# BPF.net
KiCad netlist of a schematic drawn in Altium Designer
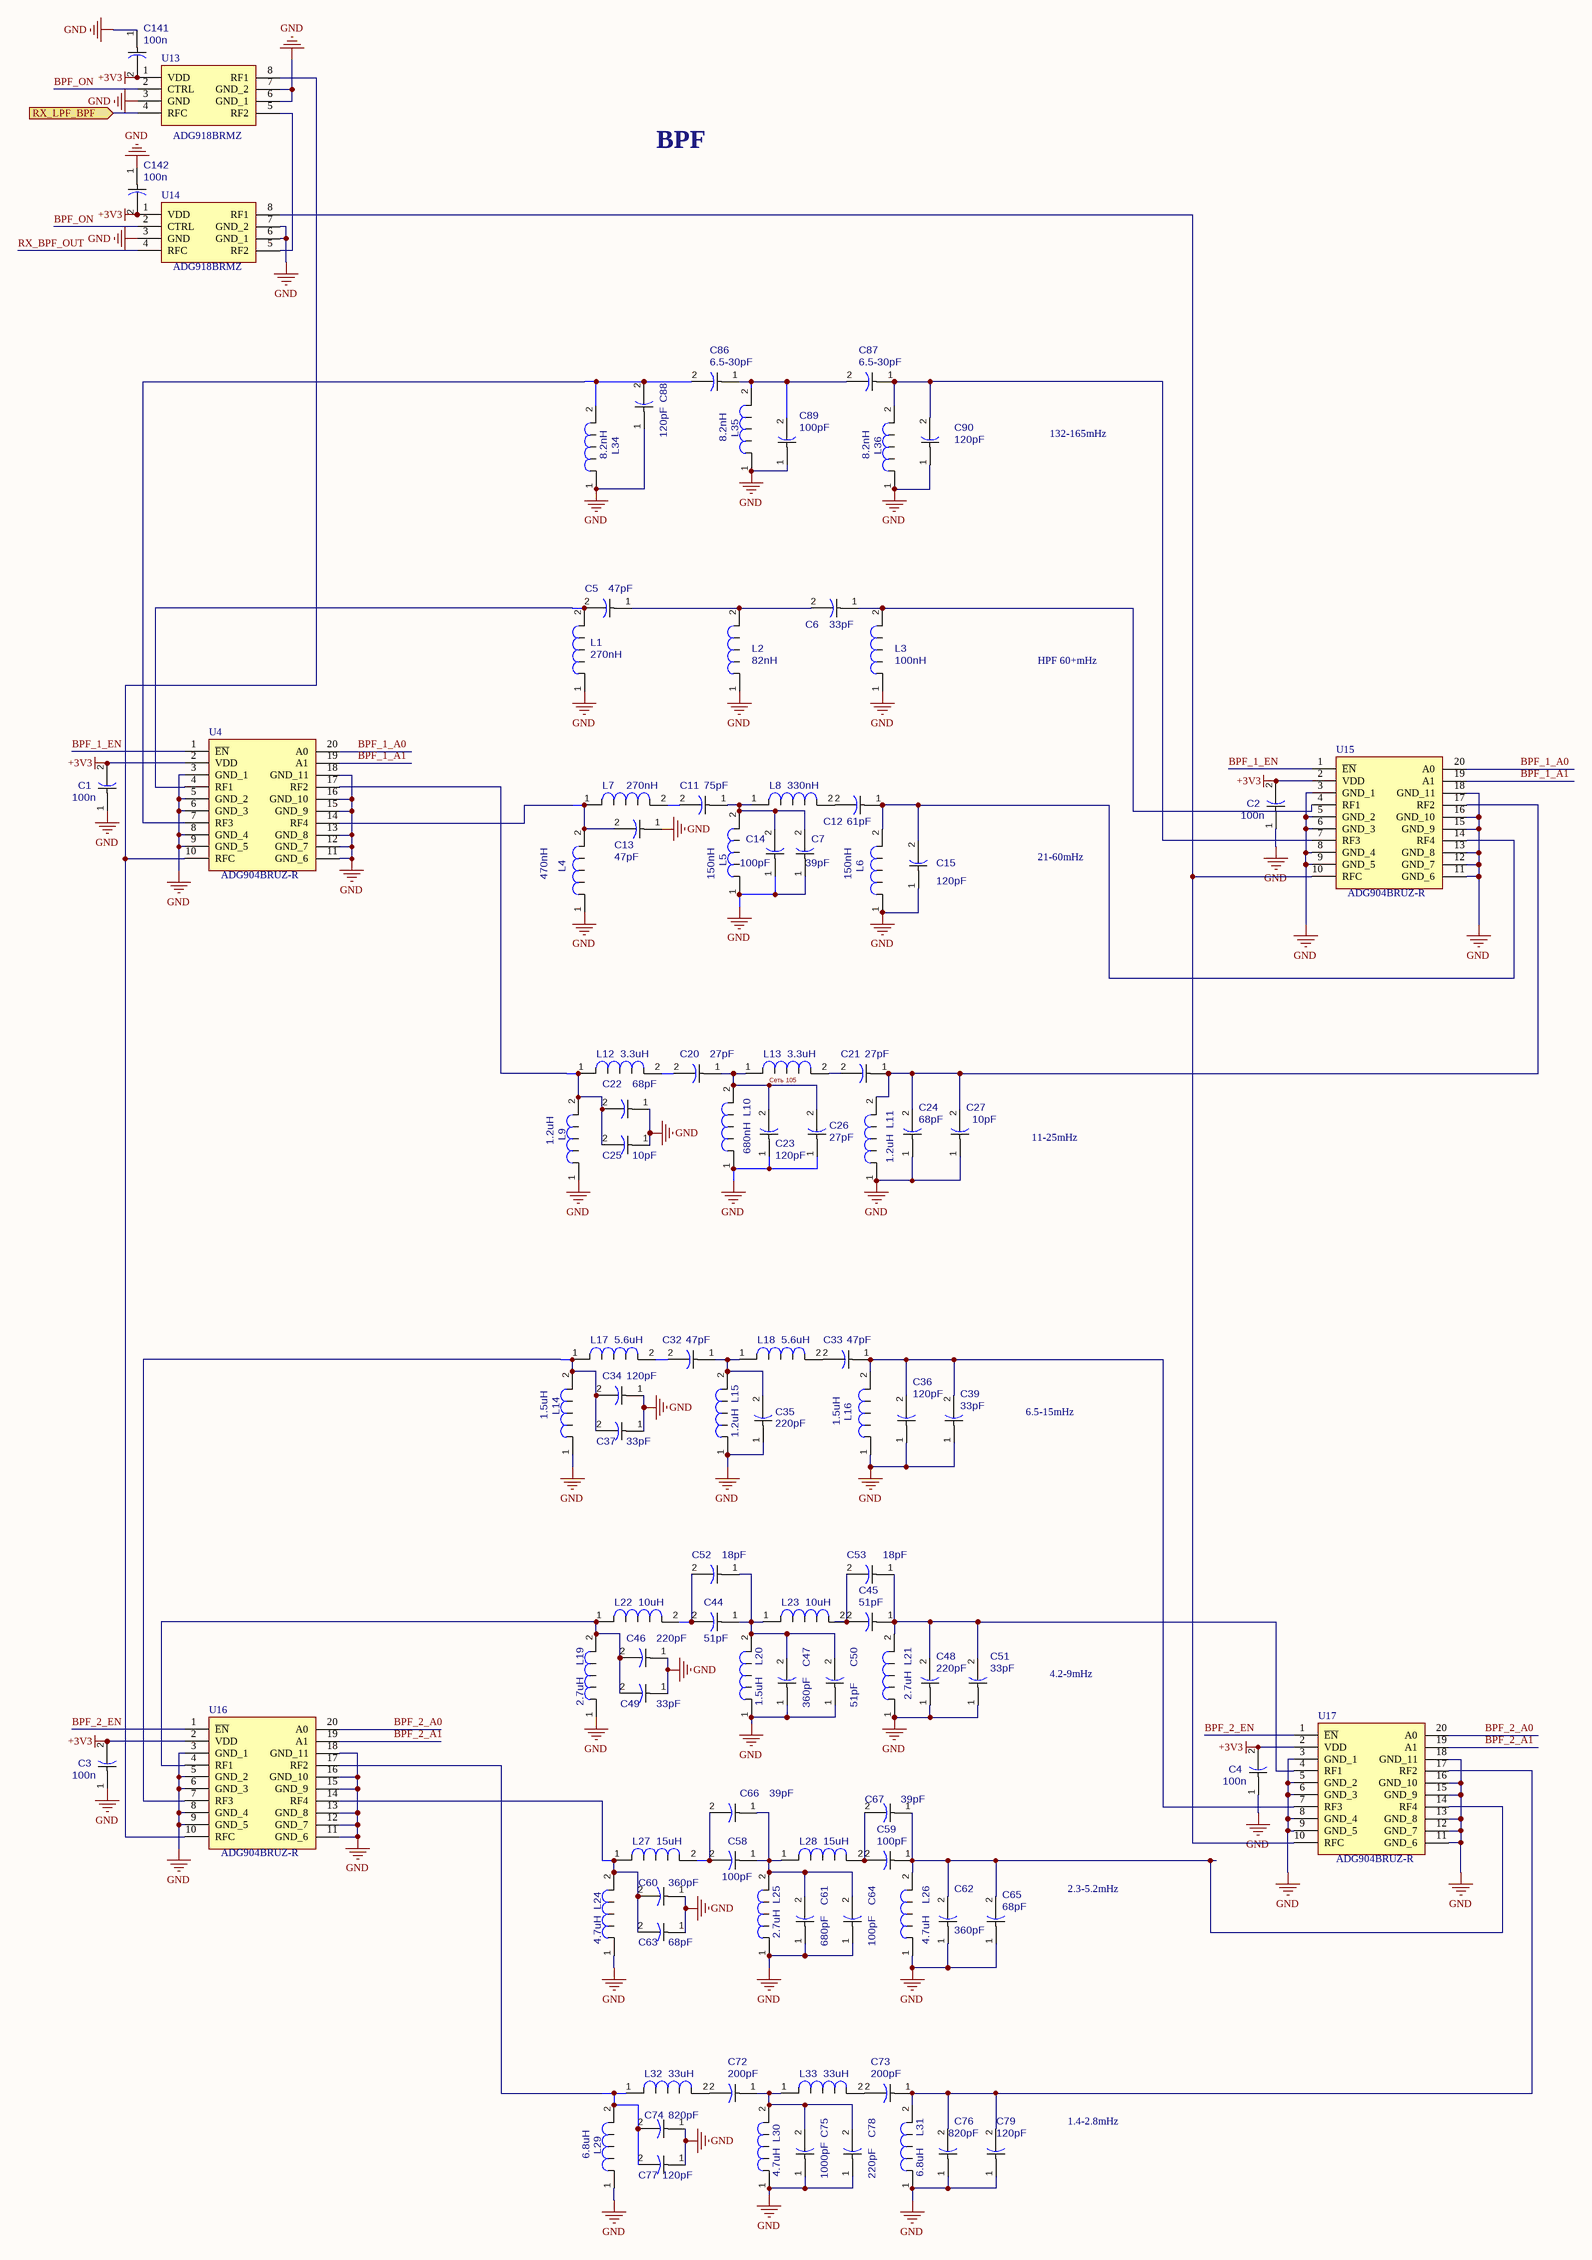
[diagram p0: BPF.SchDoc]

(export (version "E")
  (design (tool "Eeschema 10.0.6"))
  (components
    (comp (ref "C1")
      (value "100n")
      (footprint "CAP_0805")
      (description "CAP_0805")
      (libsource (lib "*") (part "CAP_0805"))
    )
    (comp (ref "C2")
      (value "100n")
      (footprint "CAP_0805")
      (description "CAP_0805")
      (libsource (lib "*") (part "CAP_0805"))
    )
    (comp (ref "C3")
      (value "100n")
      (footprint "CAP_0805")
      (description "CAP_0805")
      (libsource (lib "*") (part "CAP_0805"))
    )
    (comp (ref "C4")
      (value "100n")
      (footprint "CAP_0805")
      (description "CAP_0805")
      (libsource (lib "*") (part "CAP_0805"))
    )
    (comp (ref "C5")
      (value "47pF")
      (footprint "CAP_0805")
      (description "CAP_0805")
      (libsource (lib "*") (part "CAP_0805"))
    )
    (comp (ref "C6")
      (value "33pF")
      (footprint "CAP_0805")
      (description "CAP_0805")
      (libsource (lib "*") (part "CAP_0805"))
    )
    (comp (ref "C7")
      (value "39pF")
      (footprint "CAP_0805")
      (description "CAP_0805")
      (libsource (lib "*") (part "CAP_0805"))
    )
    (comp (ref "C11")
      (value "75pF")
      (footprint "CAP_0805")
      (description "CAP_0805")
      (libsource (lib "*") (part "CAP_0805"))
    )
    (comp (ref "C12")
      (value "61pF")
      (footprint "CAP_0805")
      (description "CAP_0805")
      (libsource (lib "*") (part "CAP_0805"))
    )
    (comp (ref "C13")
      (value "47pF")
      (footprint "CAP_0805")
      (description "CAP_0805")
      (libsource (lib "*") (part "CAP_0805"))
    )
    (comp (ref "C14")
      (value "100pF")
      (footprint "CAP_0805")
      (description "CAP_0805")
      (libsource (lib "*") (part "CAP_0805"))
    )
    (comp (ref "C15")
      (value "120pF")
      (footprint "CAP_0805")
      (description "CAP_0805")
      (libsource (lib "*") (part "CAP_0805"))
    )
    (comp (ref "C20")
      (value "27pF")
      (footprint "CAP_0805")
      (description "CAP_0805")
      (libsource (lib "*") (part "CAP_0805"))
    )
    (comp (ref "C21")
      (value "27pF")
      (footprint "CAP_0805")
      (description "CAP_0805")
      (libsource (lib "*") (part "CAP_0805"))
    )
    (comp (ref "C22")
      (value "68pF")
      (footprint "CAP_0805")
      (description "CAP_0805")
      (libsource (lib "*") (part "CAP_0805"))
    )
    (comp (ref "C23")
      (value "120pF")
      (footprint "CAP_0805")
      (description "CAP_0805")
      (libsource (lib "*") (part "CAP_0805"))
    )
    (comp (ref "C24")
      (value "68pF")
      (footprint "CAP_0805")
      (description "CAP_0805")
      (libsource (lib "*") (part "CAP_0805"))
    )
    (comp (ref "C25")
      (value "10pF")
      (footprint "CAP_0805")
      (description "CAP_0805")
      (libsource (lib "*") (part "CAP_0805"))
    )
    (comp (ref "C26")
      (value "27pF")
      (footprint "CAP_0805")
      (description "CAP_0805")
      (libsource (lib "*") (part "CAP_0805"))
    )
    (comp (ref "C27")
      (value "10pF")
      (footprint "CAP_0805")
      (description "CAP_0805")
      (libsource (lib "*") (part "CAP_0805"))
    )
    (comp (ref "C32")
      (value "47pF")
      (footprint "CAP_0805")
      (description "CAP_0805")
      (libsource (lib "*") (part "CAP_0805"))
    )
    (comp (ref "C33")
      (value "47pF")
      (footprint "CAP_0805")
      (description "CAP_0805")
      (libsource (lib "*") (part "CAP_0805"))
    )
    (comp (ref "C34")
      (value "120pF")
      (footprint "CAP_0805")
      (description "CAP_0805")
      (libsource (lib "*") (part "CAP_0805"))
    )
    (comp (ref "C35")
      (value "220pF")
      (footprint "CAP_0805")
      (description "CAP_0805")
      (libsource (lib "*") (part "CAP_0805"))
    )
    (comp (ref "C36")
      (value "120pF")
      (footprint "CAP_0805")
      (description "CAP_0805")
      (libsource (lib "*") (part "CAP_0805"))
    )
    (comp (ref "C37")
      (value "33pF")
      (footprint "CAP_0805")
      (description "CAP_0805")
      (libsource (lib "*") (part "CAP_0805"))
    )
    (comp (ref "C39")
      (value "33pF")
      (footprint "CAP_0805")
      (description "CAP_0805")
      (libsource (lib "*") (part "CAP_0805"))
    )
    (comp (ref "C44")
      (value "51pF")
      (footprint "CAP_0805")
      (description "CAP_0805")
      (libsource (lib "*") (part "CAP_0805"))
    )
    (comp (ref "C45")
      (value "51pF")
      (footprint "CAP_0805")
      (description "CAP_0805")
      (libsource (lib "*") (part "CAP_0805"))
    )
    (comp (ref "C46")
      (value "220pF")
      (footprint "CAP_0805")
      (description "CAP_0805")
      (libsource (lib "*") (part "CAP_0805"))
    )
    (comp (ref "C47")
      (value "360pF")
      (footprint "CAP_0805")
      (description "CAP_0805")
      (libsource (lib "*") (part "CAP_0805"))
    )
    (comp (ref "C48")
      (value "220pF")
      (footprint "CAP_0805")
      (description "CAP_0805")
      (libsource (lib "*") (part "CAP_0805"))
    )
    (comp (ref "C49")
      (value "33pF")
      (footprint "CAP_0805")
      (description "CAP_0805")
      (libsource (lib "*") (part "CAP_0805"))
    )
    (comp (ref "C50")
      (value "51pF")
      (footprint "CAP_0805")
      (description "CAP_0805")
      (libsource (lib "*") (part "CAP_0805"))
    )
    (comp (ref "C51")
      (value "33pF")
      (footprint "CAP_0805")
      (description "CAP_0805")
      (libsource (lib "*") (part "CAP_0805"))
    )
    (comp (ref "C52")
      (value "18pF")
      (footprint "CAP_0805")
      (description "CAP_0805")
      (libsource (lib "*") (part "CAP_0805"))
    )
    (comp (ref "C53")
      (value "18pF")
      (footprint "CAP_0805")
      (description "CAP_0805")
      (libsource (lib "*") (part "CAP_0805"))
    )
    (comp (ref "C58")
      (value "100pF")
      (footprint "CAP_0805")
      (description "CAP_0805")
      (libsource (lib "*") (part "CAP_0805"))
    )
    (comp (ref "C59")
      (value "100pF")
      (footprint "CAP_0805")
      (description "CAP_0805")
      (libsource (lib "*") (part "CAP_0805"))
    )
    (comp (ref "C60")
      (value "360pF")
      (footprint "CAP_0805")
      (description "CAP_0805")
      (libsource (lib "*") (part "CAP_0805"))
    )
    (comp (ref "C61")
      (value "680pF")
      (footprint "CAP_0805")
      (description "CAP_0805")
      (libsource (lib "*") (part "CAP_0805"))
    )
    (comp (ref "C62")
      (value "360pF")
      (footprint "CAP_0805")
      (description "CAP_0805")
      (libsource (lib "*") (part "CAP_0805"))
    )
    (comp (ref "C63")
      (value "68pF")
      (footprint "CAP_0805")
      (description "CAP_0805")
      (libsource (lib "*") (part "CAP_0805"))
    )
    (comp (ref "C64")
      (value "100pF")
      (footprint "CAP_0805")
      (description "CAP_0805")
      (libsource (lib "*") (part "CAP_0805"))
    )
    (comp (ref "C65")
      (value "68pF")
      (footprint "CAP_0805")
      (description "CAP_0805")
      (libsource (lib "*") (part "CAP_0805"))
    )
    (comp (ref "C66")
      (value "39pF")
      (footprint "CAP_0805")
      (description "CAP_0805")
      (libsource (lib "*") (part "CAP_0805"))
    )
    (comp (ref "C67")
      (value "39pF")
      (footprint "CAP_0805")
      (description "CAP_0805")
      (libsource (lib "*") (part "CAP_0805"))
    )
    (comp (ref "C72")
      (value "200pF")
      (footprint "CAP_0805")
      (description "CAP_0805")
      (libsource (lib "*") (part "CAP_0805"))
    )
    (comp (ref "C73")
      (value "200pF")
      (footprint "CAP_0805")
      (description "CAP_0805")
      (libsource (lib "*") (part "CAP_0805"))
    )
    (comp (ref "C74")
      (value "820pF")
      (footprint "CAP_0805")
      (description "CAP_0805")
      (libsource (lib "*") (part "CAP_0805"))
    )
    (comp (ref "C75")
      (value "1000pF")
      (footprint "CAP_0805")
      (description "CAP_0805")
      (libsource (lib "*") (part "CAP_0805"))
    )
    (comp (ref "C76")
      (value "820pF")
      (footprint "CAP_0805")
      (description "CAP_0805")
      (libsource (lib "*") (part "CAP_0805"))
    )
    (comp (ref "C77")
      (value "120pF")
      (footprint "CAP_0805")
      (description "CAP_0805")
      (libsource (lib "*") (part "CAP_0805"))
    )
    (comp (ref "C78")
      (value "220pF")
      (footprint "CAP_0805")
      (description "CAP_0805")
      (libsource (lib "*") (part "CAP_0805"))
    )
    (comp (ref "C79")
      (value "120pF")
      (footprint "CAP_0805")
      (description "CAP_0805")
      (libsource (lib "*") (part "CAP_0805"))
    )
    (comp (ref "C86")
      (value "6.5-30pF")
      (footprint "5025[2010]")
      (description "CAP_0805")
      (libsource (lib "*") (part "CAP_0805"))
    )
    (comp (ref "C87")
      (value "6.5-30pF")
      (footprint "5025[2010]")
      (description "CAP_0805")
      (libsource (lib "*") (part "CAP_0805"))
    )
    (comp (ref "C88")
      (value "120pF")
      (footprint "CAP_0805")
      (description "CAP_0805")
      (libsource (lib "*") (part "CAP_0805"))
    )
    (comp (ref "C89")
      (value "100pF")
      (footprint "CAP_0805")
      (description "CAP_0805")
      (libsource (lib "*") (part "CAP_0805"))
    )
    (comp (ref "C90")
      (value "120pF")
      (footprint "CAP_0805")
      (description "CAP_0805")
      (libsource (lib "*") (part "CAP_0805"))
    )
    (comp (ref "C141")
      (value "100n")
      (footprint "CAP_0805")
      (description "CAP_0805")
      (libsource (lib "*") (part "CAP_0805"))
    )
    (comp (ref "C142")
      (value "100n")
      (footprint "CAP_0805")
      (description "CAP_0805")
      (libsource (lib "*") (part "CAP_0805"))
    )
    (comp (ref "L1")
      (value "270nH")
      (footprint "IND_0805")
      (description "IND_0805")
      (libsource (lib "*") (part "IND_0805"))
    )
    (comp (ref "L2")
      (value "82nH")
      (footprint "IND_0805")
      (description "IND_0805")
      (libsource (lib "*") (part "IND_0805"))
    )
    (comp (ref "L3")
      (value "100nH")
      (footprint "IND_0805")
      (description "IND_0805")
      (libsource (lib "*") (part "IND_0805"))
    )
    (comp (ref "L4")
      (value "470nH")
      (footprint "IND_0805")
      (description "IND_0805")
      (libsource (lib "*") (part "IND_0805"))
    )
    (comp (ref "L5")
      (value "150nH")
      (footprint "IND_0805")
      (description "IND_0805")
      (libsource (lib "*") (part "IND_0805"))
    )
    (comp (ref "L6")
      (value "150nH")
      (footprint "IND_0805")
      (description "IND_0805")
      (libsource (lib "*") (part "IND_0805"))
    )
    (comp (ref "L7")
      (value "270nH")
      (footprint "IND_0805")
      (description "IND_0805")
      (libsource (lib "*") (part "IND_0805"))
    )
    (comp (ref "L8")
      (value "330nH")
      (footprint "IND_0805")
      (description "IND_0805")
      (libsource (lib "*") (part "IND_0805"))
    )
    (comp (ref "L9")
      (value "1.2uH")
      (footprint "IND_0805")
      (description "IND_0805")
      (libsource (lib "*") (part "IND_0805"))
    )
    (comp (ref "L10")
      (value "680nH")
      (footprint "IND_0805")
      (description "IND_0805")
      (libsource (lib "*") (part "IND_0805"))
    )
    (comp (ref "L11")
      (value "1.2uH")
      (footprint "IND_0805")
      (description "IND_0805")
      (libsource (lib "*") (part "IND_0805"))
    )
    (comp (ref "L12")
      (value "3.3uH")
      (footprint "IND_0805")
      (description "IND_0805")
      (libsource (lib "*") (part "IND_0805"))
    )
    (comp (ref "L13")
      (value "3.3uH")
      (footprint "IND_0805")
      (description "IND_0805")
      (libsource (lib "*") (part "IND_0805"))
    )
    (comp (ref "L14")
      (value "1.5uH")
      (footprint "IND_0805")
      (description "IND_0805")
      (libsource (lib "*") (part "IND_0805"))
    )
    (comp (ref "L15")
      (value "1.2uH")
      (footprint "IND_0805")
      (description "IND_0805")
      (libsource (lib "*") (part "IND_0805"))
    )
    (comp (ref "L16")
      (value "1.5uH")
      (footprint "IND_0805")
      (description "IND_0805")
      (libsource (lib "*") (part "IND_0805"))
    )
    (comp (ref "L17")
      (value "5.6uH")
      (footprint "IND_0805")
      (description "IND_0805")
      (libsource (lib "*") (part "IND_0805"))
    )
    (comp (ref "L18")
      (value "5.6uH")
      (footprint "IND_0805")
      (description "IND_0805")
      (libsource (lib "*") (part "IND_0805"))
    )
    (comp (ref "L19")
      (value "2.7uH")
      (footprint "IND_0805")
      (description "IND_0805")
      (libsource (lib "*") (part "IND_0805"))
    )
    (comp (ref "L20")
      (value "1.5uH")
      (footprint "IND_0805")
      (description "IND_0805")
      (libsource (lib "*") (part "IND_0805"))
    )
    (comp (ref "L21")
      (value "2.7uH")
      (footprint "IND_0805")
      (description "IND_0805")
      (libsource (lib "*") (part "IND_0805"))
    )
    (comp (ref "L22")
      (value "10uH")
      (footprint "IND_0805")
      (description "IND_0805")
      (libsource (lib "*") (part "IND_0805"))
    )
    (comp (ref "L23")
      (value "10uH")
      (footprint "IND_0805")
      (description "IND_0805")
      (libsource (lib "*") (part "IND_0805"))
    )
    (comp (ref "L24")
      (value "4.7uH")
      (footprint "IND_0805")
      (description "IND_0805")
      (libsource (lib "*") (part "IND_0805"))
    )
    (comp (ref "L25")
      (value "2.7uH")
      (footprint "IND_0805")
      (description "IND_0805")
      (libsource (lib "*") (part "IND_0805"))
    )
    (comp (ref "L26")
      (value "4.7uH")
      (footprint "IND_0805")
      (description "IND_0805")
      (libsource (lib "*") (part "IND_0805"))
    )
    (comp (ref "L27")
      (value "15uH")
      (footprint "IND_0805")
      (description "IND_0805")
      (libsource (lib "*") (part "IND_0805"))
    )
    (comp (ref "L28")
      (value "15uH")
      (footprint "IND_0805")
      (description "IND_0805")
      (libsource (lib "*") (part "IND_0805"))
    )
    (comp (ref "L29")
      (value "6.8uH")
      (footprint "IND_0805")
      (description "IND_0805")
      (libsource (lib "*") (part "IND_0805"))
    )
    (comp (ref "L30")
      (value "4.7uH")
      (footprint "IND_0805")
      (description "IND_0805")
      (libsource (lib "*") (part "IND_0805"))
    )
    (comp (ref "L31")
      (value "6.8uH")
      (footprint "IND_0805")
      (description "IND_0805")
      (libsource (lib "*") (part "IND_0805"))
    )
    (comp (ref "L32")
      (value "33uH")
      (footprint "IND_0805")
      (description "IND_0805")
      (libsource (lib "*") (part "IND_0805"))
    )
    (comp (ref "L33")
      (value "33uH")
      (footprint "IND_0805")
      (description "IND_0805")
      (libsource (lib "*") (part "IND_0805"))
    )
    (comp (ref "L34")
      (value "8.2nH")
      (footprint "IND_0805")
      (description "IND_0805")
      (libsource (lib "*") (part "IND_0805"))
    )
    (comp (ref "L35")
      (value "8.2nH")
      (footprint "IND_0805")
      (description "IND_0805")
      (libsource (lib "*") (part "IND_0805"))
    )
    (comp (ref "L36")
      (value "8.2nH")
      (footprint "IND_0805")
      (description "IND_0805")
      (libsource (lib "*") (part "IND_0805"))
    )
    (comp (ref "U4")
      (value "ADG904BRUZ-R")
      (footprint "SamacSys:SOP65P640X120-20N")
      (description "Integrated Circuit")
      (fields
        (field (name "MOUSER PART NUMBER") "584-ADG904BRUZ-R")
        (field (name "RS PART NUMBER") "5385019P")
      )
      (libsource (lib "*") (part "ADG904BRUZ-R"))
    )
    (comp (ref "U13")
      (value "ADG918BRMZ")
      (footprint "SamacSys:SOP65P490X110-8N")
      (description "Integrated Circuit")
      (fields (field (name "MOUSER PART NUMBER") "584-ADG918BRMZ") (field (name "RS PART NUMBER") "4969212P"))
      (libsource (lib "*") (part "ADG918BRMZ"))
    )
    (comp (ref "U14")
      (value "ADG918BRMZ")
      (footprint "SamacSys:SOP65P490X110-8N")
      (description "Integrated Circuit")
      (fields (field (name "MOUSER PART NUMBER") "584-ADG918BRMZ") (field (name "RS PART NUMBER") "4969212P"))
      (libsource (lib "*") (part "ADG918BRMZ"))
    )
    (comp (ref "U15")
      (value "ADG904BRUZ-R")
      (footprint "SamacSys:SOP65P640X120-20N")
      (description "Integrated Circuit")
      (fields
        (field (name "MOUSER PART NUMBER") "584-ADG904BRUZ-R")
        (field (name "RS PART NUMBER") "5385019P")
      )
      (libsource (lib "*") (part "ADG904BRUZ-R"))
    )
    (comp (ref "U16")
      (value "ADG904BRUZ-R")
      (footprint "SamacSys:SOP65P640X120-20N")
      (description "Integrated Circuit")
      (fields
        (field (name "MOUSER PART NUMBER") "584-ADG904BRUZ-R")
        (field (name "RS PART NUMBER") "5385019P")
      )
      (libsource (lib "*") (part "ADG904BRUZ-R"))
    )
    (comp (ref "U17")
      (value "ADG904BRUZ-R")
      (footprint "SamacSys:SOP65P640X120-20N")
      (description "Integrated Circuit")
      (fields
        (field (name "MOUSER PART NUMBER") "584-ADG904BRUZ-R")
        (field (name "RS PART NUMBER") "5385019P")
      )
      (libsource (lib "*") (part "ADG904BRUZ-R"))
    )
  )
  (nets
    (net (code "1") (name "+3V3") (class "Default")
      (node (ref "C1") (pin "2") (pinfunction "2_2") (pintype "passive"))
      (node (ref "C141") (pin "2") (pinfunction "2_2") (pintype "passive"))
      (node (ref "C142") (pin "2") (pinfunction "2_2") (pintype "passive"))
      (node (ref "C2") (pin "2") (pinfunction "2_2") (pintype "passive"))
      (node (ref "C3") (pin "2") (pinfunction "2_2") (pintype "passive"))
      (node (ref "C4") (pin "2") (pinfunction "2_2") (pintype "passive"))
      (node (ref "U13") (pin "1") (pinfunction "VDD_1") (pintype "power_in"))
      (node (ref "U14") (pin "1") (pinfunction "VDD_1") (pintype "power_in"))
      (node (ref "U15") (pin "2") (pinfunction "VDD_2") (pintype "passive"))
      (node (ref "U16") (pin "2") (pinfunction "VDD_2") (pintype "passive"))
      (node (ref "U17") (pin "2") (pinfunction "VDD_2") (pintype "passive"))
      (node (ref "U4") (pin "2") (pinfunction "VDD_2") (pintype "passive"))
    )
    (net (code "2") (name "/BPF_1_A0") (class "Default")
      (node (ref "U15") (pin "20") (pinfunction "A0_20") (pintype "passive"))
      (node (ref "U4") (pin "20") (pinfunction "A0_20") (pintype "passive"))
    )
    (net (code "3") (name "/BPF_1_A1") (class "Default")
      (node (ref "U15") (pin "19") (pinfunction "A1_19") (pintype "passive"))
      (node (ref "U4") (pin "19") (pinfunction "A1_19") (pintype "passive"))
    )
    (net (code "4") (name "/BPF_1_EN") (class "Default")
      (node (ref "U15") (pin "1") (pinfunction "~{EN}_1") (pintype "passive"))
      (node (ref "U4") (pin "1") (pinfunction "~{EN}_1") (pintype "passive"))
    )
    (net (code "5") (name "/BPF_2_A0") (class "Default")
      (node (ref "U16") (pin "20") (pinfunction "A0_20") (pintype "passive"))
      (node (ref "U17") (pin "20") (pinfunction "A0_20") (pintype "passive"))
    )
    (net (code "6") (name "/BPF_2_A1") (class "Default")
      (node (ref "U16") (pin "19") (pinfunction "A1_19") (pintype "passive"))
      (node (ref "U17") (pin "19") (pinfunction "A1_19") (pintype "passive"))
    )
    (net (code "7") (name "/BPF_2_EN") (class "Default")
      (node (ref "U16") (pin "1") (pinfunction "~{EN}_1") (pintype "passive"))
      (node (ref "U17") (pin "1") (pinfunction "~{EN}_1") (pintype "passive"))
    )
    (net (code "8") (name "/BPF_ON") (class "Default")
      (node (ref "U13") (pin "2") (pinfunction "CTRL_2") (pintype "passive"))
      (node (ref "U14") (pin "2") (pinfunction "CTRL_2") (pintype "passive"))
    )
    (net (code "9") (name "/RX_BPF_OUT") (class "Default")
      (node (ref "U14") (pin "4") (pinfunction "RFC_4") (pintype "passive"))
    )
    (net (code "10") (name "/RX_LPF_BPF") (class "Default")
      (node (ref "U13") (pin "4") (pinfunction "RFC_4") (pintype "passive"))
    )
    (net (code "11") (name "/Сеть 105") (class "Default")
      (node (ref "C20") (pin "1") (pinfunction "1_1") (pintype "passive"))
      (node (ref "C23") (pin "2") (pinfunction "2_2") (pintype "passive"))
      (node (ref "C26") (pin "2") (pinfunction "2_2") (pintype "passive"))
      (node (ref "L10") (pin "2") (pinfunction "2_2") (pintype "passive"))
      (node (ref "L13") (pin "1") (pinfunction "1_1") (pintype "passive"))
    )
    (net (code "12") (name "GND") (class "Default")
      (node (ref "C1") (pin "1") (pinfunction "1_1") (pintype "passive"))
      (node (ref "C13") (pin "1") (pinfunction "1_1") (pintype "passive"))
      (node (ref "C14") (pin "1") (pinfunction "1_1") (pintype "passive"))
      (node (ref "C141") (pin "1") (pinfunction "1_1") (pintype "passive"))
      (node (ref "C142") (pin "1") (pinfunction "1_1") (pintype "passive"))
      (node (ref "C15") (pin "1") (pinfunction "1_1") (pintype "passive"))
      (node (ref "C2") (pin "1") (pinfunction "1_1") (pintype "passive"))
      (node (ref "C22") (pin "1") (pinfunction "1_1") (pintype "passive"))
      (node (ref "C23") (pin "1") (pinfunction "1_1") (pintype "passive"))
      (node (ref "C24") (pin "1") (pinfunction "1_1") (pintype "passive"))
      (node (ref "C25") (pin "1") (pinfunction "1_1") (pintype "passive"))
      (node (ref "C26") (pin "1") (pinfunction "1_1") (pintype "passive"))
      (node (ref "C27") (pin "1") (pinfunction "1_1") (pintype "passive"))
      (node (ref "C3") (pin "1") (pinfunction "1_1") (pintype "passive"))
      (node (ref "C34") (pin "1") (pinfunction "1_1") (pintype "passive"))
      (node (ref "C35") (pin "1") (pinfunction "1_1") (pintype "passive"))
      (node (ref "C36") (pin "1") (pinfunction "1_1") (pintype "passive"))
      (node (ref "C37") (pin "1") (pinfunction "1_1") (pintype "passive"))
      (node (ref "C39") (pin "1") (pinfunction "1_1") (pintype "passive"))
      (node (ref "C4") (pin "1") (pinfunction "1_1") (pintype "passive"))
      (node (ref "C46") (pin "1") (pinfunction "1_1") (pintype "passive"))
      (node (ref "C47") (pin "1") (pinfunction "1_1") (pintype "passive"))
      (node (ref "C48") (pin "1") (pinfunction "1_1") (pintype "passive"))
      (node (ref "C49") (pin "1") (pinfunction "1_1") (pintype "passive"))
      (node (ref "C50") (pin "1") (pinfunction "1_1") (pintype "passive"))
      (node (ref "C51") (pin "1") (pinfunction "1_1") (pintype "passive"))
      (node (ref "C60") (pin "1") (pinfunction "1_1") (pintype "passive"))
      (node (ref "C61") (pin "1") (pinfunction "1_1") (pintype "passive"))
      (node (ref "C62") (pin "1") (pinfunction "1_1") (pintype "passive"))
      (node (ref "C63") (pin "1") (pinfunction "1_1") (pintype "passive"))
      (node (ref "C64") (pin "1") (pinfunction "1_1") (pintype "passive"))
      (node (ref "C65") (pin "1") (pinfunction "1_1") (pintype "passive"))
      (node (ref "C7") (pin "1") (pinfunction "1_1") (pintype "passive"))
      (node (ref "C74") (pin "1") (pinfunction "1_1") (pintype "passive"))
      (node (ref "C75") (pin "1") (pinfunction "1_1") (pintype "passive"))
      (node (ref "C76") (pin "1") (pinfunction "1_1") (pintype "passive"))
      (node (ref "C77") (pin "1") (pinfunction "1_1") (pintype "passive"))
      (node (ref "C78") (pin "1") (pinfunction "1_1") (pintype "passive"))
      (node (ref "C79") (pin "1") (pinfunction "1_1") (pintype "passive"))
      (node (ref "C88") (pin "1") (pinfunction "1_1") (pintype "passive"))
      (node (ref "C89") (pin "1") (pinfunction "1_1") (pintype "passive"))
      (node (ref "C90") (pin "1") (pinfunction "1_1") (pintype "passive"))
      (node (ref "L1") (pin "1") (pinfunction "1_1") (pintype "passive"))
      (node (ref "L10") (pin "1") (pinfunction "1_1") (pintype "passive"))
      (node (ref "L11") (pin "1") (pinfunction "1_1") (pintype "passive"))
      (node (ref "L14") (pin "1") (pinfunction "1_1") (pintype "passive"))
      (node (ref "L15") (pin "1") (pinfunction "1_1") (pintype "passive"))
      (node (ref "L16") (pin "1") (pinfunction "1_1") (pintype "passive"))
      (node (ref "L19") (pin "1") (pinfunction "1_1") (pintype "passive"))
      (node (ref "L2") (pin "1") (pinfunction "1_1") (pintype "passive"))
      (node (ref "L20") (pin "1") (pinfunction "1_1") (pintype "passive"))
      (node (ref "L21") (pin "1") (pinfunction "1_1") (pintype "passive"))
      (node (ref "L24") (pin "1") (pinfunction "1_1") (pintype "passive"))
      (node (ref "L25") (pin "1") (pinfunction "1_1") (pintype "passive"))
      (node (ref "L26") (pin "1") (pinfunction "1_1") (pintype "passive"))
      (node (ref "L29") (pin "1") (pinfunction "1_1") (pintype "passive"))
      (node (ref "L3") (pin "1") (pinfunction "1_1") (pintype "passive"))
      (node (ref "L30") (pin "1") (pinfunction "1_1") (pintype "passive"))
      (node (ref "L31") (pin "1") (pinfunction "1_1") (pintype "passive"))
      (node (ref "L34") (pin "1") (pinfunction "1_1") (pintype "passive"))
      (node (ref "L35") (pin "1") (pinfunction "1_1") (pintype "passive"))
      (node (ref "L36") (pin "1") (pinfunction "1_1") (pintype "passive"))
      (node (ref "L4") (pin "1") (pinfunction "1_1") (pintype "passive"))
      (node (ref "L5") (pin "1") (pinfunction "1_1") (pintype "passive"))
      (node (ref "L6") (pin "1") (pinfunction "1_1") (pintype "passive"))
      (node (ref "L9") (pin "1") (pinfunction "1_1") (pintype "passive"))
      (node (ref "U13") (pin "3") (pinfunction "GND_3") (pintype "power_in"))
      (node (ref "U13") (pin "6") (pinfunction "GND_1_6") (pintype "power_in"))
      (node (ref "U13") (pin "7") (pinfunction "GND_2_7") (pintype "power_in"))
      (node (ref "U14") (pin "3") (pinfunction "GND_3") (pintype "power_in"))
      (node (ref "U14") (pin "6") (pinfunction "GND_1_6") (pintype "power_in"))
      (node (ref "U14") (pin "7") (pinfunction "GND_2_7") (pintype "power_in"))
      (node (ref "U15") (pin "11") (pinfunction "GND_6_11") (pintype "passive"))
      (node (ref "U15") (pin "12") (pinfunction "GND_7_12") (pintype "passive"))
      (node (ref "U15") (pin "13") (pinfunction "GND_8_13") (pintype "passive"))
      (node (ref "U15") (pin "15") (pinfunction "GND_9_15") (pintype "passive"))
      (node (ref "U15") (pin "16") (pinfunction "GND_10_16") (pintype "passive"))
      (node (ref "U15") (pin "18") (pinfunction "GND_11_18") (pintype "passive"))
      (node (ref "U15") (pin "3") (pinfunction "GND_1_3") (pintype "passive"))
      (node (ref "U15") (pin "5") (pinfunction "GND_2_5") (pintype "passive"))
      (node (ref "U15") (pin "6") (pinfunction "GND_3_6") (pintype "passive"))
      (node (ref "U15") (pin "8") (pinfunction "GND_4_8") (pintype "passive"))
      (node (ref "U15") (pin "9") (pinfunction "GND_5_9") (pintype "passive"))
      (node (ref "U16") (pin "11") (pinfunction "GND_6_11") (pintype "passive"))
      (node (ref "U16") (pin "12") (pinfunction "GND_7_12") (pintype "passive"))
      (node (ref "U16") (pin "13") (pinfunction "GND_8_13") (pintype "passive"))
      (node (ref "U16") (pin "15") (pinfunction "GND_9_15") (pintype "passive"))
      (node (ref "U16") (pin "16") (pinfunction "GND_10_16") (pintype "passive"))
      (node (ref "U16") (pin "18") (pinfunction "GND_11_18") (pintype "passive"))
      (node (ref "U16") (pin "3") (pinfunction "GND_1_3") (pintype "passive"))
      (node (ref "U16") (pin "5") (pinfunction "GND_2_5") (pintype "passive"))
      (node (ref "U16") (pin "6") (pinfunction "GND_3_6") (pintype "passive"))
      (node (ref "U16") (pin "8") (pinfunction "GND_4_8") (pintype "passive"))
      (node (ref "U16") (pin "9") (pinfunction "GND_5_9") (pintype "passive"))
      (node (ref "U17") (pin "11") (pinfunction "GND_6_11") (pintype "passive"))
      (node (ref "U17") (pin "12") (pinfunction "GND_7_12") (pintype "passive"))
      (node (ref "U17") (pin "13") (pinfunction "GND_8_13") (pintype "passive"))
      (node (ref "U17") (pin "15") (pinfunction "GND_9_15") (pintype "passive"))
      (node (ref "U17") (pin "16") (pinfunction "GND_10_16") (pintype "passive"))
      (node (ref "U17") (pin "18") (pinfunction "GND_11_18") (pintype "passive"))
      (node (ref "U17") (pin "3") (pinfunction "GND_1_3") (pintype "passive"))
      (node (ref "U17") (pin "5") (pinfunction "GND_2_5") (pintype "passive"))
      (node (ref "U17") (pin "6") (pinfunction "GND_3_6") (pintype "passive"))
      (node (ref "U17") (pin "8") (pinfunction "GND_4_8") (pintype "passive"))
      (node (ref "U17") (pin "9") (pinfunction "GND_5_9") (pintype "passive"))
      (node (ref "U4") (pin "11") (pinfunction "GND_6_11") (pintype "passive"))
      (node (ref "U4") (pin "12") (pinfunction "GND_7_12") (pintype "passive"))
      (node (ref "U4") (pin "13") (pinfunction "GND_8_13") (pintype "passive"))
      (node (ref "U4") (pin "15") (pinfunction "GND_9_15") (pintype "passive"))
      (node (ref "U4") (pin "16") (pinfunction "GND_10_16") (pintype "passive"))
      (node (ref "U4") (pin "18") (pinfunction "GND_11_18") (pintype "passive"))
      (node (ref "U4") (pin "3") (pinfunction "GND_1_3") (pintype "passive"))
      (node (ref "U4") (pin "5") (pinfunction "GND_2_5") (pintype "passive"))
      (node (ref "U4") (pin "6") (pinfunction "GND_3_6") (pintype "passive"))
      (node (ref "U4") (pin "8") (pinfunction "GND_4_8") (pintype "passive"))
      (node (ref "U4") (pin "9") (pinfunction "GND_5_9") (pintype "passive"))
    )
    (net (code "13") (name "Net-(C5-Pad1)") (class "Default")
      (node (ref "C5") (pin "1") (pinfunction "1_1") (pintype "passive"))
      (node (ref "C6") (pin "2") (pinfunction "2_2") (pintype "passive"))
      (node (ref "L2") (pin "2") (pinfunction "2_2") (pintype "passive"))
    )
    (net (code "14") (name "Net-(C11-Pad1)") (class "Default")
      (node (ref "C11") (pin "1") (pinfunction "1_1") (pintype "passive"))
      (node (ref "C14") (pin "2") (pinfunction "2_2") (pintype "passive"))
      (node (ref "C7") (pin "2") (pinfunction "2_2") (pintype "passive"))
      (node (ref "L5") (pin "2") (pinfunction "2_2") (pintype "passive"))
      (node (ref "L8") (pin "1") (pinfunction "1_1") (pintype "passive"))
    )
    (net (code "15") (name "Net-(C11-Pad2)") (class "Default")
      (node (ref "C11") (pin "2") (pinfunction "2_2") (pintype "passive"))
      (node (ref "L7") (pin "2") (pinfunction "2_2") (pintype "passive"))
    )
    (net (code "16") (name "Net-(C12-Pad2)") (class "Default")
      (node (ref "C12") (pin "2") (pinfunction "2_2") (pintype "passive"))
      (node (ref "L8") (pin "2") (pinfunction "2_2") (pintype "passive"))
    )
    (net (code "17") (name "Net-(C20-Pad2)") (class "Default")
      (node (ref "C20") (pin "2") (pinfunction "2_2") (pintype "passive"))
      (node (ref "L12") (pin "2") (pinfunction "2_2") (pintype "passive"))
    )
    (net (code "18") (name "Net-(C21-Pad2)") (class "Default")
      (node (ref "C21") (pin "2") (pinfunction "2_2") (pintype "passive"))
      (node (ref "L13") (pin "2") (pinfunction "2_2") (pintype "passive"))
    )
    (net (code "19") (name "Net-(C32-Pad1)") (class "Default")
      (node (ref "C32") (pin "1") (pinfunction "1_1") (pintype "passive"))
      (node (ref "C35") (pin "2") (pinfunction "2_2") (pintype "passive"))
      (node (ref "L15") (pin "2") (pinfunction "2_2") (pintype "passive"))
      (node (ref "L18") (pin "1") (pinfunction "1_1") (pintype "passive"))
    )
    (net (code "20") (name "Net-(C32-Pad2)") (class "Default")
      (node (ref "C32") (pin "2") (pinfunction "2_2") (pintype "passive"))
      (node (ref "L17") (pin "2") (pinfunction "2_2") (pintype "passive"))
    )
    (net (code "21") (name "Net-(C33-Pad2)") (class "Default")
      (node (ref "C33") (pin "2") (pinfunction "2_2") (pintype "passive"))
      (node (ref "L18") (pin "2") (pinfunction "2_2") (pintype "passive"))
    )
    (net (code "22") (name "Net-(C44-Pad1)") (class "Default")
      (node (ref "C44") (pin "1") (pinfunction "1_1") (pintype "passive"))
      (node (ref "C47") (pin "2") (pinfunction "2_2") (pintype "passive"))
      (node (ref "C50") (pin "2") (pinfunction "2_2") (pintype "passive"))
      (node (ref "C52") (pin "1") (pinfunction "1_1") (pintype "passive"))
      (node (ref "L20") (pin "2") (pinfunction "2_2") (pintype "passive"))
      (node (ref "L23") (pin "1") (pinfunction "1_1") (pintype "passive"))
    )
    (net (code "23") (name "Net-(C44-Pad2)") (class "Default")
      (node (ref "C44") (pin "2") (pinfunction "2_2") (pintype "passive"))
      (node (ref "C52") (pin "2") (pinfunction "2_2") (pintype "passive"))
      (node (ref "L22") (pin "2") (pinfunction "2_2") (pintype "passive"))
    )
    (net (code "24") (name "Net-(C45-Pad2)") (class "Default")
      (node (ref "C45") (pin "2") (pinfunction "2_2") (pintype "passive"))
      (node (ref "C53") (pin "2") (pinfunction "2_2") (pintype "passive"))
      (node (ref "L23") (pin "2") (pinfunction "2_2") (pintype "passive"))
    )
    (net (code "25") (name "Net-(C58-Pad1)") (class "Default")
      (node (ref "C58") (pin "1") (pinfunction "1_1") (pintype "passive"))
      (node (ref "C61") (pin "2") (pinfunction "2_2") (pintype "passive"))
      (node (ref "C64") (pin "2") (pinfunction "2_2") (pintype "passive"))
      (node (ref "C66") (pin "1") (pinfunction "1_1") (pintype "passive"))
      (node (ref "L25") (pin "2") (pinfunction "2_2") (pintype "passive"))
      (node (ref "L28") (pin "1") (pinfunction "1_1") (pintype "passive"))
    )
    (net (code "26") (name "Net-(C58-Pad2)") (class "Default")
      (node (ref "C58") (pin "2") (pinfunction "2_2") (pintype "passive"))
      (node (ref "C66") (pin "2") (pinfunction "2_2") (pintype "passive"))
      (node (ref "L27") (pin "2") (pinfunction "2_2") (pintype "passive"))
    )
    (net (code "27") (name "Net-(C59-Pad2)") (class "Default")
      (node (ref "C59") (pin "2") (pinfunction "2_2") (pintype "passive"))
      (node (ref "C67") (pin "2") (pinfunction "2_2") (pintype "passive"))
      (node (ref "L28") (pin "2") (pinfunction "2_2") (pintype "passive"))
    )
    (net (code "28") (name "Net-(C72-Pad1)") (class "Default")
      (node (ref "C72") (pin "1") (pinfunction "1_1") (pintype "passive"))
      (node (ref "C75") (pin "2") (pinfunction "2_2") (pintype "passive"))
      (node (ref "C78") (pin "2") (pinfunction "2_2") (pintype "passive"))
      (node (ref "L30") (pin "2") (pinfunction "2_2") (pintype "passive"))
      (node (ref "L33") (pin "1") (pinfunction "1_1") (pintype "passive"))
    )
    (net (code "29") (name "Net-(C72-Pad2)") (class "Default")
      (node (ref "C72") (pin "2") (pinfunction "2_2") (pintype "passive"))
      (node (ref "L32") (pin "2") (pinfunction "2_2") (pintype "passive"))
    )
    (net (code "30") (name "Net-(C73-Pad2)") (class "Default")
      (node (ref "C73") (pin "2") (pinfunction "2_2") (pintype "passive"))
      (node (ref "L33") (pin "2") (pinfunction "2_2") (pintype "passive"))
    )
    (net (code "31") (name "Net-(C86-Pad1)") (class "Default")
      (node (ref "C86") (pin "1") (pinfunction "1_1") (pintype "passive"))
      (node (ref "C87") (pin "2") (pinfunction "2_2") (pintype "passive"))
      (node (ref "C89") (pin "2") (pinfunction "2_2") (pintype "passive"))
      (node (ref "L35") (pin "2") (pinfunction "2_2") (pintype "passive"))
    )
    (net (code "32") (name "Net-(U4-RF1)") (class "Default")
      (node (ref "C5") (pin "2") (pinfunction "2_2") (pintype "passive"))
      (node (ref "L1") (pin "2") (pinfunction "2_2") (pintype "passive"))
      (node (ref "U4") (pin "4") (pinfunction "RF1_4") (pintype "passive"))
    )
    (net (code "33") (name "Net-(U4-RF2)") (class "Default")
      (node (ref "C22") (pin "2") (pinfunction "2_2") (pintype "passive"))
      (node (ref "C25") (pin "2") (pinfunction "2_2") (pintype "passive"))
      (node (ref "L12") (pin "1") (pinfunction "1_1") (pintype "passive"))
      (node (ref "L9") (pin "2") (pinfunction "2_2") (pintype "passive"))
      (node (ref "U4") (pin "17") (pinfunction "RF2_17") (pintype "passive"))
    )
    (net (code "34") (name "Net-(U4-RF3)") (class "Default")
      (node (ref "C86") (pin "2") (pinfunction "2_2") (pintype "passive"))
      (node (ref "C88") (pin "2") (pinfunction "2_2") (pintype "passive"))
      (node (ref "L34") (pin "2") (pinfunction "2_2") (pintype "passive"))
      (node (ref "U4") (pin "7") (pinfunction "RF3_7") (pintype "passive"))
    )
    (net (code "35") (name "Net-(U4-RF4)") (class "Default")
      (node (ref "C13") (pin "2") (pinfunction "2_2") (pintype "passive"))
      (node (ref "L4") (pin "2") (pinfunction "2_2") (pintype "passive"))
      (node (ref "L7") (pin "1") (pinfunction "1_1") (pintype "passive"))
      (node (ref "U4") (pin "14") (pinfunction "RF4_14") (pintype "passive"))
    )
    (net (code "36") (name "Net-(U13-RF1)") (class "Default")
      (node (ref "U13") (pin "8") (pinfunction "RF1_8") (pintype "passive"))
      (node (ref "U16") (pin "10") (pinfunction "RFC_10") (pintype "passive"))
      (node (ref "U4") (pin "10") (pinfunction "RFC_10") (pintype "passive"))
    )
    (net (code "37") (name "Net-(U13-RF2)") (class "Default")
      (node (ref "U13") (pin "5") (pinfunction "RF2_5") (pintype "passive"))
      (node (ref "U14") (pin "5") (pinfunction "RF2_5") (pintype "passive"))
    )
    (net (code "38") (name "Net-(U14-RF1)") (class "Default")
      (node (ref "U14") (pin "8") (pinfunction "RF1_8") (pintype "passive"))
      (node (ref "U15") (pin "10") (pinfunction "RFC_10") (pintype "passive"))
      (node (ref "U17") (pin "10") (pinfunction "RFC_10") (pintype "passive"))
    )
    (net (code "39") (name "Net-(U15-RF1)") (class "Default")
      (node (ref "C6") (pin "1") (pinfunction "1_1") (pintype "passive"))
      (node (ref "L3") (pin "2") (pinfunction "2_2") (pintype "passive"))
      (node (ref "U15") (pin "4") (pinfunction "RF1_4") (pintype "passive"))
    )
    (net (code "40") (name "Net-(U15-RF2)") (class "Default")
      (node (ref "C21") (pin "1") (pinfunction "1_1") (pintype "passive"))
      (node (ref "C24") (pin "2") (pinfunction "2_2") (pintype "passive"))
      (node (ref "C27") (pin "2") (pinfunction "2_2") (pintype "passive"))
      (node (ref "L11") (pin "2") (pinfunction "2_2") (pintype "passive"))
      (node (ref "U15") (pin "17") (pinfunction "RF2_17") (pintype "passive"))
    )
    (net (code "41") (name "Net-(U15-RF3)") (class "Default")
      (node (ref "C87") (pin "1") (pinfunction "1_1") (pintype "passive"))
      (node (ref "C90") (pin "2") (pinfunction "2_2") (pintype "passive"))
      (node (ref "L36") (pin "2") (pinfunction "2_2") (pintype "passive"))
      (node (ref "U15") (pin "7") (pinfunction "RF3_7") (pintype "passive"))
    )
    (net (code "42") (name "Net-(U15-RF4)") (class "Default")
      (node (ref "C12") (pin "1") (pinfunction "1_1") (pintype "passive"))
      (node (ref "C15") (pin "2") (pinfunction "2_2") (pintype "passive"))
      (node (ref "L6") (pin "2") (pinfunction "2_2") (pintype "passive"))
      (node (ref "U15") (pin "14") (pinfunction "RF4_14") (pintype "passive"))
    )
    (net (code "43") (name "Net-(U16-RF1)") (class "Default")
      (node (ref "C46") (pin "2") (pinfunction "2_2") (pintype "passive"))
      (node (ref "C49") (pin "2") (pinfunction "2_2") (pintype "passive"))
      (node (ref "L19") (pin "2") (pinfunction "2_2") (pintype "passive"))
      (node (ref "L22") (pin "1") (pinfunction "1_1") (pintype "passive"))
      (node (ref "U16") (pin "4") (pinfunction "RF1_4") (pintype "passive"))
    )
    (net (code "44") (name "Net-(U16-RF2)") (class "Default")
      (node (ref "C74") (pin "2") (pinfunction "2_2") (pintype "passive"))
      (node (ref "C77") (pin "2") (pinfunction "2_2") (pintype "passive"))
      (node (ref "L29") (pin "2") (pinfunction "2_2") (pintype "passive"))
      (node (ref "L32") (pin "1") (pinfunction "1_1") (pintype "passive"))
      (node (ref "U16") (pin "17") (pinfunction "RF2_17") (pintype "passive"))
    )
    (net (code "45") (name "Net-(U16-RF3)") (class "Default")
      (node (ref "C34") (pin "2") (pinfunction "2_2") (pintype "passive"))
      (node (ref "C37") (pin "2") (pinfunction "2_2") (pintype "passive"))
      (node (ref "L14") (pin "2") (pinfunction "2_2") (pintype "passive"))
      (node (ref "L17") (pin "1") (pinfunction "1_1") (pintype "passive"))
      (node (ref "U16") (pin "7") (pinfunction "RF3_7") (pintype "passive"))
    )
    (net (code "46") (name "Net-(U16-RF4)") (class "Default")
      (node (ref "C60") (pin "2") (pinfunction "2_2") (pintype "passive"))
      (node (ref "C63") (pin "2") (pinfunction "2_2") (pintype "passive"))
      (node (ref "L24") (pin "2") (pinfunction "2_2") (pintype "passive"))
      (node (ref "L27") (pin "1") (pinfunction "1_1") (pintype "passive"))
      (node (ref "U16") (pin "14") (pinfunction "RF4_14") (pintype "passive"))
    )
    (net (code "47") (name "Net-(U17-RF1)") (class "Default")
      (node (ref "C45") (pin "1") (pinfunction "1_1") (pintype "passive"))
      (node (ref "C48") (pin "2") (pinfunction "2_2") (pintype "passive"))
      (node (ref "C51") (pin "2") (pinfunction "2_2") (pintype "passive"))
      (node (ref "C53") (pin "1") (pinfunction "1_1") (pintype "passive"))
      (node (ref "L21") (pin "2") (pinfunction "2_2") (pintype "passive"))
      (node (ref "U17") (pin "4") (pinfunction "RF1_4") (pintype "passive"))
    )
    (net (code "48") (name "Net-(U17-RF2)") (class "Default")
      (node (ref "C73") (pin "1") (pinfunction "1_1") (pintype "passive"))
      (node (ref "C76") (pin "2") (pinfunction "2_2") (pintype "passive"))
      (node (ref "C79") (pin "2") (pinfunction "2_2") (pintype "passive"))
      (node (ref "L31") (pin "2") (pinfunction "2_2") (pintype "passive"))
      (node (ref "U17") (pin "17") (pinfunction "RF2_17") (pintype "passive"))
    )
    (net (code "49") (name "Net-(U17-RF3)") (class "Default")
      (node (ref "C33") (pin "1") (pinfunction "1_1") (pintype "passive"))
      (node (ref "C36") (pin "2") (pinfunction "2_2") (pintype "passive"))
      (node (ref "C39") (pin "2") (pinfunction "2_2") (pintype "passive"))
      (node (ref "L16") (pin "2") (pinfunction "2_2") (pintype "passive"))
      (node (ref "U17") (pin "7") (pinfunction "RF3_7") (pintype "passive"))
    )
    (net (code "50") (name "Net-(U17-RF4)") (class "Default")
      (node (ref "C59") (pin "1") (pinfunction "1_1") (pintype "passive"))
      (node (ref "C62") (pin "2") (pinfunction "2_2") (pintype "passive"))
      (node (ref "C65") (pin "2") (pinfunction "2_2") (pintype "passive"))
      (node (ref "C67") (pin "1") (pinfunction "1_1") (pintype "passive"))
      (node (ref "L26") (pin "2") (pinfunction "2_2") (pintype "passive"))
      (node (ref "U17") (pin "14") (pinfunction "RF4_14") (pintype "passive"))
    )
  )
)
